# buck_regulator.net
KiCad netlist of a schematic drawn in EAGLE
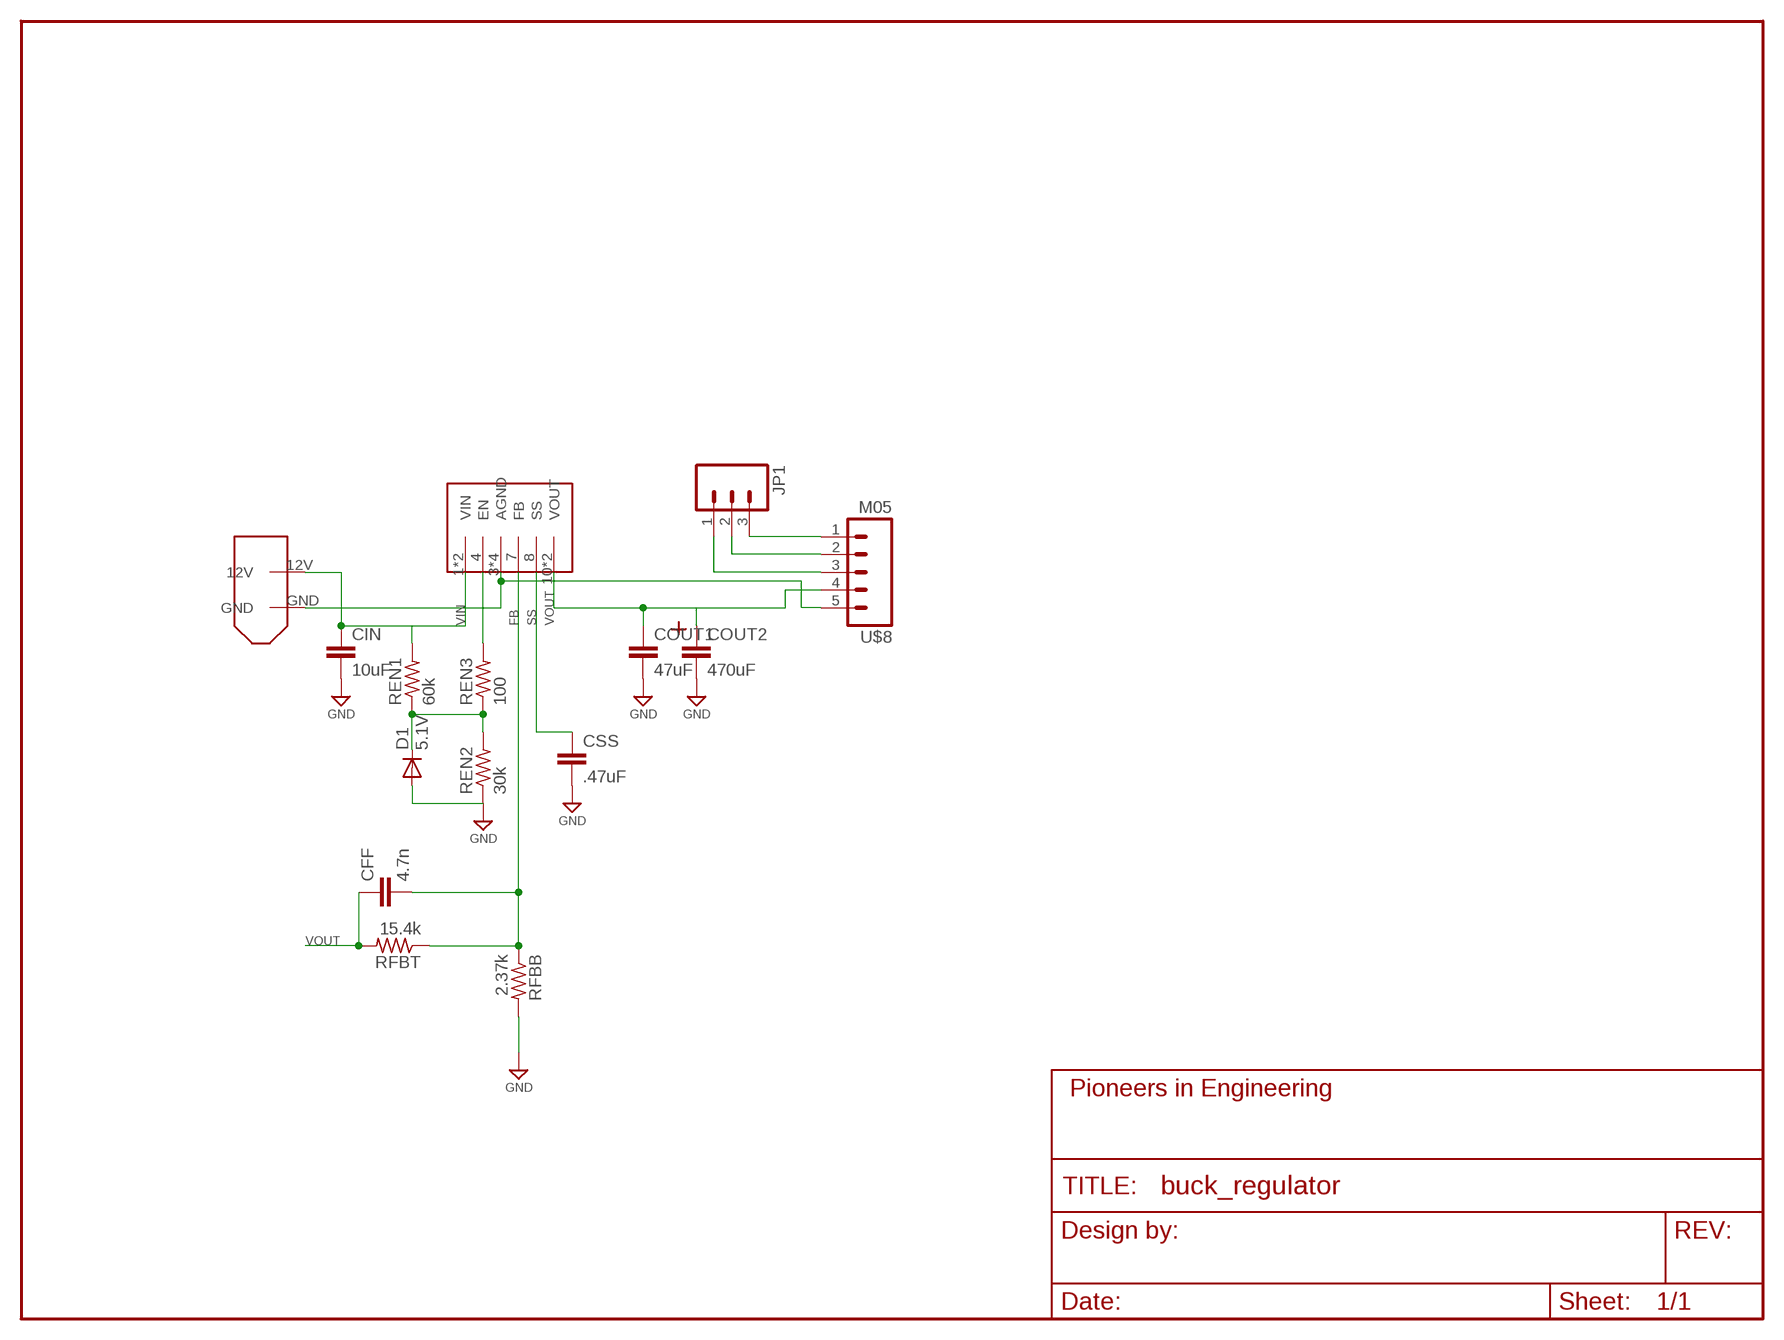
[diagram p0: schematic, sheet 1]

(export (version "E")
  (design (tool "Eeschema 10.0.6"))
  (components
    (comp (ref "CFF")
      (value "4.7n")
      (footprint "eagle-import:0603-CAP")
      (libsource (lib "eagle-import") (part "pie_CAP0603-CAP"))
    )
    (comp (ref "CIN")
      (value "10uF")
      (footprint "eagle-import:0603-CAP")
      (libsource (lib "eagle-import") (part "pie_CAP0603-CAP"))
    )
    (comp (ref "COUT1")
      (value "47uF")
      (footprint "eagle-import:1206")
      (libsource (lib "eagle-import") (part "CAP1206"))
    )
    (comp (ref "COUT2")
      (value "470uF")
      (footprint "eagle-import:TANT_CASE_E")
      (libsource (lib "eagle-import") (part "TANT_CASE_E"))
    )
    (comp (ref "CSS")
      (value ".47uF")
      (footprint "eagle-import:0603-CAP")
      (libsource (lib "eagle-import") (part "pie_CAP0603-CAP"))
    )
    (comp (ref "D1")
      (value "5.1V")
      (footprint "eagle-import:SOD-323")
      (libsource (lib "eagle-import") (part "DIODESOD"))
    )
    (comp (ref "JP1")
      (value "M03MTA1X3")
      (footprint "eagle-import:1X03")
      (libsource (lib "eagle-import") (part "M03MTA1X3"))
    )
    (comp (ref "REN1")
      (value "60k")
      (footprint "eagle-import:R0603")
      (libsource (lib "eagle-import") (part "R-US_R0603"))
    )
    (comp (ref "REN2")
      (value "30k")
      (footprint "eagle-import:R0603")
      (libsource (lib "eagle-import") (part "R-US_R0603"))
    )
    (comp (ref "REN3")
      (value "100")
      (footprint "eagle-import:R0603")
      (libsource (lib "eagle-import") (part "R-US_R0603"))
    )
    (comp (ref "RFBB")
      (value "2.37k")
      (footprint "eagle-import:R0603")
      (libsource (lib "eagle-import") (part "R-US_R0603"))
    )
    (comp (ref "RFBT")
      (value "15.4k")
      (footprint "eagle-import:R0603")
      (libsource (lib "eagle-import") (part "R-US_R0603"))
    )
    (comp (ref "U$1")
      (value "LMZ12010")
      (footprint "eagle-import:LMZ12010")
      (libsource (lib "eagle-import") (part "LMZ12010"))
    )
    (comp (ref "U$2")
      (value "XT60CONNECTOR")
      (footprint "eagle-import:XT60CONNECTOR")
      (libsource (lib "eagle-import") (part "XT60CONNECTOR"))
    )
    (comp (ref "U$8")
      (value "M05")
      (footprint "eagle-import:1X05-MTA")
      (libsource (lib "eagle-import") (part "M05"))
    )
  )
  (nets
    (net (code "1") (name "/FB") (class "Default")
      (node (ref "CFF") (pin "2") (pinfunction "2_2") (pintype "passive"))
      (node (ref "RFBB") (pin "1") (pinfunction "1_1") (pintype "passive"))
      (node (ref "RFBT") (pin "1") (pinfunction "1_1") (pintype "passive"))
      (node (ref "U$1") (pin "7") (pinfunction "FB_7") (pintype "bidirectional"))
    )
    (net (code "2") (name "/SS") (class "Default")
      (node (ref "CSS") (pin "1") (pinfunction "1_1") (pintype "passive"))
      (node (ref "U$1") (pin "8") (pinfunction "SS_8") (pintype "bidirectional"))
    )
    (net (code "3") (name "/VIN") (class "Default")
      (node (ref "CIN") (pin "1") (pinfunction "1_1") (pintype "passive"))
      (node (ref "REN1") (pin "2") (pinfunction "2_2") (pintype "passive"))
      (node (ref "U$1") (pin "1") (pinfunction "VIN_1") (pintype "bidirectional"))
      (node (ref "U$1") (pin "2") (pinfunction "VIN_2") (pintype "bidirectional"))
      (node (ref "U$2") (pin "12V") (pinfunction "12V_12V") (pintype "bidirectional"))
    )
    (net (code "4") (name "/VOUT") (class "Default")
      (node (ref "CFF") (pin "1") (pinfunction "1_1") (pintype "passive"))
      (node (ref "COUT1") (pin "1") (pinfunction "1_1") (pintype "passive"))
      (node (ref "COUT2") (pin "POS") (pinfunction "POS_POS") (pintype "passive"))
      (node (ref "RFBT") (pin "2") (pinfunction "2_2") (pintype "passive"))
      (node (ref "U$1") (pin "10") (pinfunction "VOUT_10") (pintype "bidirectional"))
      (node (ref "U$1") (pin "11") (pinfunction "VOUT_11") (pintype "bidirectional"))
      (node (ref "U$8") (pin "4") (pinfunction "4_4") (pintype "passive"))
    )
    (net (code "5") (name "GND") (class "Default")
      (node (ref "CIN") (pin "2") (pinfunction "2_2") (pintype "passive"))
      (node (ref "COUT1") (pin "2") (pinfunction "2_2") (pintype "passive"))
      (node (ref "COUT2") (pin "NEG") (pinfunction "NEG_NEG") (pintype "passive"))
      (node (ref "CSS") (pin "2") (pinfunction "2_2") (pintype "passive"))
      (node (ref "D1") (pin "2") (pinfunction "A_2") (pintype "passive"))
      (node (ref "REN2") (pin "1") (pinfunction "1_1") (pintype "passive"))
      (node (ref "RFBB") (pin "2") (pinfunction "2_2") (pintype "passive"))
      (node (ref "U$1") (pin "3") (pinfunction "AGND_3") (pintype "bidirectional"))
      (node (ref "U$1") (pin "5") (pinfunction "AGND_5") (pintype "bidirectional"))
      (node (ref "U$1") (pin "6") (pinfunction "AGND_6") (pintype "bidirectional"))
      (node (ref "U$1") (pin "GND") (pinfunction "AGND_GND") (pintype "bidirectional"))
      (node (ref "U$2") (pin "GND") (pinfunction "GND_GND") (pintype "bidirectional"))
      (node (ref "U$8") (pin "5") (pinfunction "5_5") (pintype "passive"))
    )
    (net (code "6") (name "Net-(D1-C)") (class "Default")
      (node (ref "D1") (pin "1") (pinfunction "C_1") (pintype "passive"))
      (node (ref "REN1") (pin "1") (pinfunction "1_1") (pintype "passive"))
      (node (ref "REN2") (pin "2") (pinfunction "2_2") (pintype "passive"))
      (node (ref "REN3") (pin "1") (pinfunction "1_1") (pintype "passive"))
    )
    (net (code "7") (name "Net-(JP1-Pad1)") (class "Default")
      (node (ref "JP1") (pin "1") (pinfunction "1_1") (pintype "passive"))
      (node (ref "U$8") (pin "3") (pinfunction "3_3") (pintype "passive"))
    )
    (net (code "8") (name "Net-(JP1-Pad2)") (class "Default")
      (node (ref "JP1") (pin "2") (pinfunction "2_2") (pintype "passive"))
      (node (ref "U$8") (pin "2") (pinfunction "2_2") (pintype "passive"))
    )
    (net (code "9") (name "Net-(JP1-Pad3)") (class "Default")
      (node (ref "JP1") (pin "3") (pinfunction "3_3") (pintype "passive"))
      (node (ref "U$8") (pin "1") (pinfunction "1_1") (pintype "passive"))
    )
    (net (code "10") (name "Net-(U$1-EN)") (class "Default")
      (node (ref "REN3") (pin "2") (pinfunction "2_2") (pintype "passive"))
      (node (ref "U$1") (pin "4") (pinfunction "EN_4") (pintype "bidirectional"))
    )
  )
)
